# Vcc.net
KiCad netlist of a schematic drawn in Altium Designer
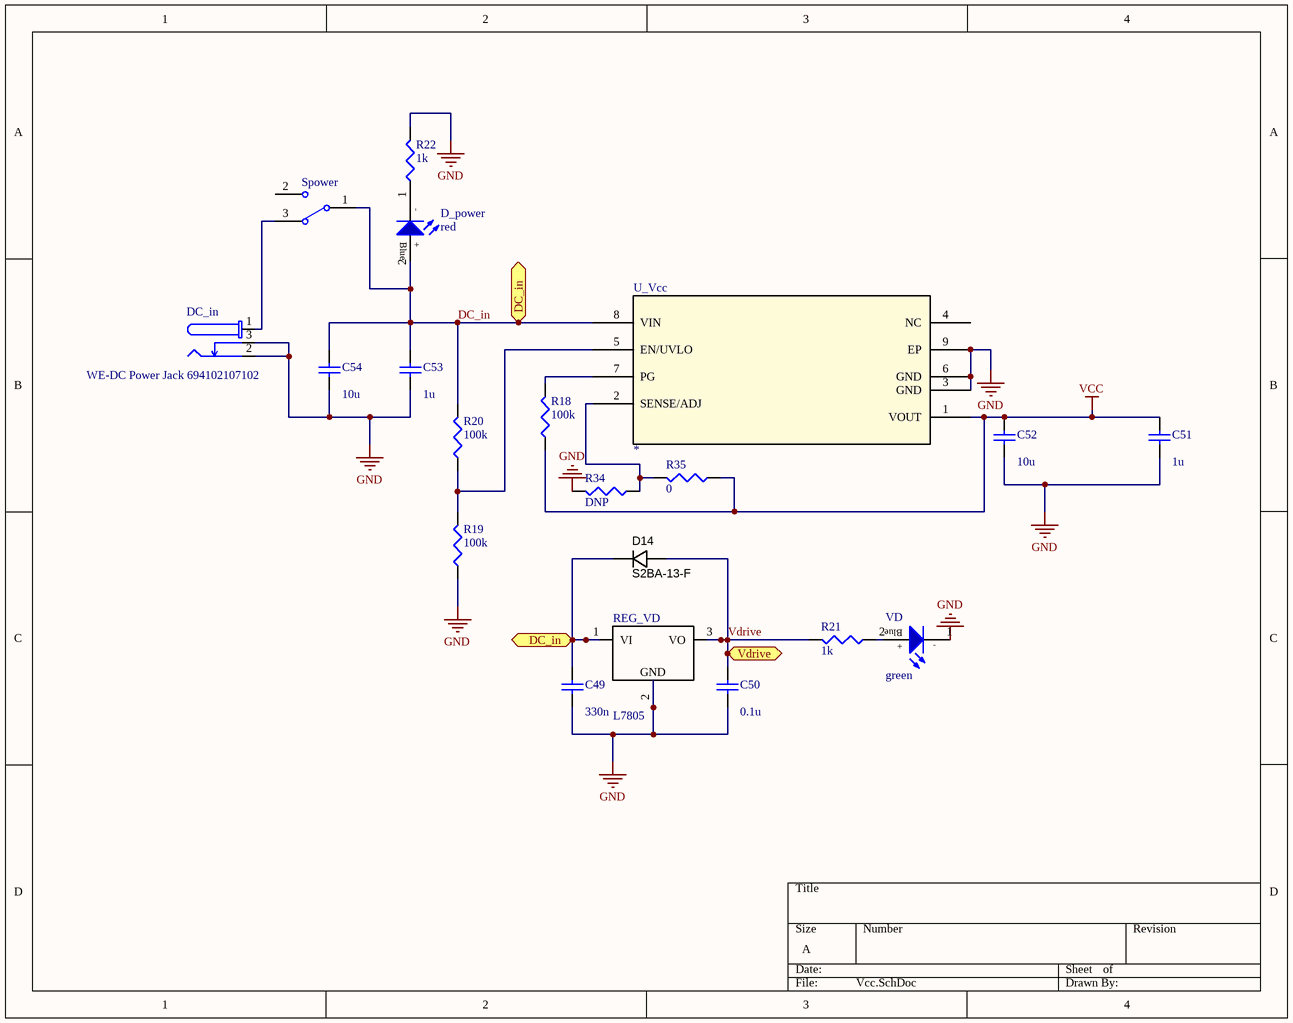
[diagram p0: Vcc.SchDoc]

(export (version "E")
  (design (tool "Eeschema 10.0.6"))
  (components
    (comp (ref "C49")
      (value "330n")
      (footprint "0805")
      (description "Ceramic Chip Capacitor - Standard")
      (fields (field (name "PUBLISHER") "Altium Limited"))
      (libsource (lib "KEMET Chip Capacitor") (part "C0805"))
    )
    (comp (ref "C50")
      (value "0.1u")
      (footprint "0603")
      (description "Ceramic Chip Capacitor - Standard")
      (fields (field (name "PUBLISHER") "Altium Limited"))
      (libsource (lib "KEMET Chip Capacitor") (part "C0603"))
    )
    (comp (ref "C51")
      (value "1u")
      (footprint "0603")
      (description "Ceramic Chip Capacitor - Standard")
      (fields (field (name "PUBLISHER") "Altium Limited"))
      (libsource (lib "KEMET Chip Capacitor") (part "C0603"))
    )
    (comp (ref "C52")
      (value "10u")
      (footprint "0805")
      (description "Ceramic Chip Capacitor - Standard")
      (fields (field (name "PUBLISHER") "Altium Limited"))
      (libsource (lib "KEMET Chip Capacitor") (part "C0805"))
    )
    (comp (ref "C53")
      (value "1u")
      (footprint "0603")
      (description "Ceramic Chip Capacitor - Standard")
      (fields (field (name "PUBLISHER") "Altium Limited"))
      (libsource (lib "KEMET Chip Capacitor") (part "C0603"))
    )
    (comp (ref "C54")
      (value "10u")
      (footprint "0805")
      (description "Ceramic Chip Capacitor - Standard")
      (fields (field (name "PUBLISHER") "Altium Limited"))
      (libsource (lib "KEMET Chip Capacitor") (part "C0805"))
    )
    (comp (ref "D14")
      (value "100V; 1.5A")
      (footprint "DO-214AC")
      (description "Diode SMD 100V 1.5A SMA")
      (fields (field (name "MANUFACTURER PART NUMBER 1") "S2BA-13-F"))
      (libsource (lib "PBL - Diodes") (part "DIODE_100V_1.5A_SMA"))
    )
    (comp (ref "DC_in")
      (value "WE-DC Power Jack 694102107102")
      (footprint "694102107102")
      (description "WR-DC_DC Power Jack_Right Angled_SMT")
      (fields
        (field (name "MANUFACTURER") "Würth Elektronik eiSos GmbH")
        (field (name "PARTNO") "694102107102")
        (field (name "CREATED BY") "Karrer Zheng")
      )
      (libsource (lib "DC_Power_Jack_rev15b") (part "WE-DC Power Jack 694102107102"))
    )
    (comp (ref "D_power")
      (value "red")
      (footprint "WL-SMCW_0603")
      (description "WL-SMCW SMD chip LED top view mono-color waterclear, 0603, Blue")
      (fields
        (field (name "PARTNO") "150060BS75000")
        (field (name "MANUFACTURER") "Wurth Elektronik")
        (field (name "CREATED BY") "Baojun Chen")
      )
      (libsource (lib "ALTIUM-WL-SMCW-rev16a") (part "WL-SMCW 0603, 150060BS75000"))
    )
    (comp (ref "R18")
      (value "100k")
      (footprint "J1-0603")
      (description "Resistor")
      (fields (field (name "PUBLISHER") "Altium Limited"))
      (libsource (lib "Miscellaneous Devices") (part "Res3"))
    )
    (comp (ref "R19")
      (value "100k")
      (footprint "J1-0603")
      (description "Resistor")
      (fields (field (name "PUBLISHER") "Altium Limited"))
      (libsource (lib "Miscellaneous Devices") (part "Res3"))
    )
    (comp (ref "R20")
      (value "100k")
      (footprint "J1-0603")
      (description "Resistor")
      (fields (field (name "PUBLISHER") "Altium Limited"))
      (libsource (lib "Miscellaneous Devices") (part "Res3"))
    )
    (comp (ref "R21")
      (value "1k")
      (footprint "J1-0603")
      (description "Resistor")
      (fields (field (name "PUBLISHER") "Altium Limited"))
      (libsource (lib "Miscellaneous Devices") (part "Res3"))
    )
    (comp (ref "R22")
      (value "1k")
      (footprint "J1-0603")
      (description "Resistor")
      (fields (field (name "PUBLISHER") "Altium Limited"))
      (libsource (lib "Miscellaneous Devices") (part "Res3"))
    )
    (comp (ref "R34")
      (value "DNP")
      (footprint "J1-0603")
      (description "Resistor")
      (fields (field (name "PUBLISHER") "Altium Limited"))
      (libsource (lib "Miscellaneous Devices") (part "Res3"))
    )
    (comp (ref "R35")
      (value "0")
      (footprint "J1-0603")
      (description "Resistor")
      (fields (field (name "PUBLISHER") "Altium Limited"))
      (libsource (lib "Miscellaneous Devices") (part "Res3"))
    )
    (comp (ref "REG_VD")
      (value "L7805")
      (footprint "DPAK")
      (description "LINEAR REGULATOR 5.0V")
      (libsource (lib "vh_altium_library") (part "L7805-DPAK"))
    )
    (comp (ref "Spower")
      (value "~")
      (footprint "450301014042")
      (description "WS-SLTV 10x2.5 mm THT")
      (fields (field (name "PART NUMBER") "450301014042") (field (name "PUBLISHER") "Wurth Elektronik"))
      (libsource (lib "ALTIUM-WS-SLTV-rev17a") (part "450301014042"))
    )
    (comp (ref "U_Vcc")
      (value "*")
      (footprint "RD_8_2")
      (description "Imported")
      (libsource (lib "2017-06-28_17-50-06") (part "ADP7104ARDZ-R7"))
    )
    (comp (ref "VD")
      (value "green")
      (footprint "WL-SMCW_0603")
      (description "WL-SMCW SMD chip LED top view mono-color waterclear, 0603, Blue")
      (fields
        (field (name "PARTNO") "150060BS75000")
        (field (name "MANUFACTURER") "Wurth Elektronik")
        (field (name "CREATED BY") "Baojun Chen")
      )
      (libsource (lib "ALTIUM-WL-SMCW-rev16a") (part "WL-SMCW 0603, 150060BS75000"))
    )
  )
  (nets
    (net (code "1") (name "/DC_in") (class "Default")
      (node (ref "C49") (pin "1") (pinfunction "1_1") (pintype "passive"))
      (node (ref "C53") (pin "1") (pinfunction "1_1") (pintype "passive"))
      (node (ref "C54") (pin "1") (pinfunction "1_1") (pintype "passive"))
      (node (ref "D14") (pin "K") (pinfunction "K_K") (pintype "passive"))
      (node (ref "D_power") (pin "2") (pinfunction "+_2") (pintype "passive"))
      (node (ref "R20") (pin "2") (pinfunction "2_2") (pintype "passive"))
      (node (ref "REG_VD") (pin "1") (pinfunction "VI_1") (pintype "passive"))
      (node (ref "Spower") (pin "1") (pinfunction "COM_1") (pintype "passive"))
      (node (ref "U_Vcc") (pin "8") (pinfunction "VIN_8") (pintype "passive"))
    )
    (net (code "2") (name "/Vdrive") (class "Default")
      (node (ref "C50") (pin "2") (pinfunction "2_2") (pintype "passive"))
      (node (ref "D14") (pin "A") (pinfunction "A_A") (pintype "passive"))
      (node (ref "R21") (pin "2") (pinfunction "2_2") (pintype "passive"))
      (node (ref "REG_VD") (pin "3") (pinfunction "VO_3") (pintype "passive"))
    )
    (net (code "3") (name "GND") (class "Default")
      (node (ref "C49") (pin "2") (pinfunction "2_2") (pintype "passive"))
      (node (ref "C50") (pin "1") (pinfunction "1_1") (pintype "passive"))
      (node (ref "C51") (pin "1") (pinfunction "1_1") (pintype "passive"))
      (node (ref "C52") (pin "2") (pinfunction "2_2") (pintype "passive"))
      (node (ref "C53") (pin "2") (pinfunction "2_2") (pintype "passive"))
      (node (ref "C54") (pin "2") (pinfunction "2_2") (pintype "passive"))
      (node (ref "DC_in") (pin "2") (pinfunction "2_2") (pintype "power_in"))
      (node (ref "DC_in") (pin "3") (pinfunction "3_3") (pintype "power_in"))
      (node (ref "R19") (pin "1") (pinfunction "1_1") (pintype "passive"))
      (node (ref "R22") (pin "2") (pinfunction "2_2") (pintype "passive"))
      (node (ref "R34") (pin "2") (pinfunction "2_2") (pintype "passive"))
      (node (ref "REG_VD") (pin "2") (pintype "passive"))
      (node (ref "U_Vcc") (pin "3") (pinfunction "GND_3") (pintype "passive"))
      (node (ref "U_Vcc") (pin "6") (pinfunction "GND_6") (pintype "passive"))
      (node (ref "U_Vcc") (pin "9") (pinfunction "EP_9") (pintype "passive"))
      (node (ref "VD") (pin "1") (pinfunction "-_1") (pintype "passive"))
    )
    (net (code "4") (name "Net-(DC_in-Pad1)") (class "Default")
      (node (ref "DC_in") (pin "1") (pinfunction "1_1") (pintype "power_in"))
      (node (ref "Spower") (pin "3") (pinfunction "3_3") (pintype "passive"))
    )
    (net (code "5") (name "Net-(D_power--)") (class "Default")
      (node (ref "D_power") (pin "1") (pinfunction "-_1") (pintype "passive"))
      (node (ref "R22") (pin "1") (pinfunction "1_1") (pintype "passive"))
    )
    (net (code "6") (name "Net-(U_Vcc-EN{slash}UVLO)") (class "Default")
      (node (ref "R19") (pin "2") (pinfunction "2_2") (pintype "passive"))
      (node (ref "R20") (pin "1") (pinfunction "1_1") (pintype "passive"))
      (node (ref "U_Vcc") (pin "5") (pinfunction "EN/UVLO_5") (pintype "passive"))
    )
    (net (code "7") (name "Net-(U_Vcc-PG)") (class "Default")
      (node (ref "R18") (pin "2") (pinfunction "2_2") (pintype "passive"))
      (node (ref "U_Vcc") (pin "7") (pinfunction "PG_7") (pintype "passive"))
    )
    (net (code "8") (name "Net-(U_Vcc-SENSE{slash}ADJ)") (class "Default")
      (node (ref "R34") (pin "1") (pinfunction "1_1") (pintype "passive"))
      (node (ref "R35") (pin "2") (pinfunction "2_2") (pintype "passive"))
      (node (ref "U_Vcc") (pin "2") (pinfunction "SENSE/ADJ_2") (pintype "passive"))
    )
    (net (code "9") (name "Net-(VD-+)") (class "Default")
      (node (ref "R21") (pin "1") (pinfunction "1_1") (pintype "passive"))
      (node (ref "VD") (pin "2") (pinfunction "+_2") (pintype "passive"))
    )
    (net (code "10") (name "VCC") (class "Default")
      (node (ref "C51") (pin "2") (pinfunction "2_2") (pintype "passive"))
      (node (ref "C52") (pin "1") (pinfunction "1_1") (pintype "passive"))
      (node (ref "R18") (pin "1") (pinfunction "1_1") (pintype "passive"))
      (node (ref "R35") (pin "1") (pinfunction "1_1") (pintype "passive"))
      (node (ref "U_Vcc") (pin "1") (pinfunction "VOUT_1") (pintype "passive"))
    )
    (net (code "11") (name "unconnected-(Spower-Pad2)") (class "Default")
      (node (ref "Spower") (pin "2") (pinfunction "2_2") (pintype "passive"))
    )
    (net (code "12") (name "unconnected-(U_Vcc-NC-Pad4)") (class "Default")
      (node (ref "U_Vcc") (pin "4") (pinfunction "NC_4") (pintype "passive"))
    )
  )
)
